# CON_MC_XMC_J12_64PIN.net
KiCad netlist of a schematic drawn in Altium Designer
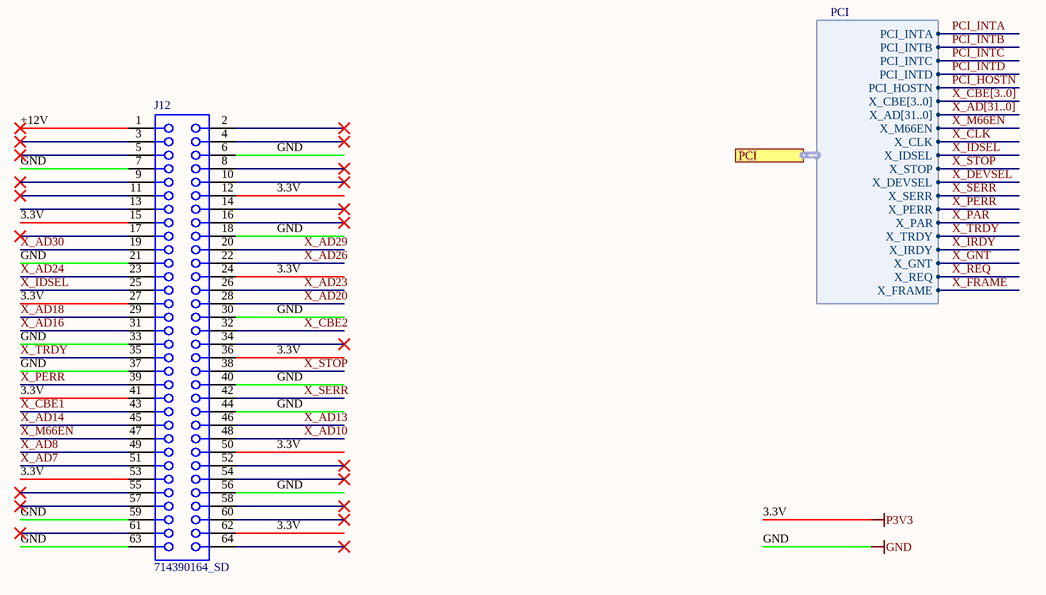
[diagram p0: CON_MC_XMC_J12_64PIN.SchDoc]

(export (version "E")
  (design (tool "Eeschema 10.0.6"))
  (components
    (comp (ref "J12")
      (value "714390164_SD")
      (footprint "BTB1-2V64F")
      (description "Board-to-Board Connector, Vertical, 2-Row, Pitch 1mm, 64-Position, Female")
      (fields (field (name "PUBLISHER") "Altium"))
      (libsource (lib "Altium Shanghai") (part "CMP-0001-00081-1"))
    )
  )
  (nets
    (net (code "21") (name "/+12V") (class "Default")
      (node (ref "J12") (pin "1") (pinfunction "1_1") (pintype "passive+no_connect"))
    )
    (net (code "28") (name "/X_AD7") (class "Default")
      (node (ref "J12") (pin "51") (pinfunction "51_51") (pintype "passive"))
    )
    (net (code "29") (name "/X_AD8") (class "Default")
      (node (ref "J12") (pin "49") (pinfunction "49_49") (pintype "passive"))
    )
    (net (code "30") (name "/X_AD10") (class "Default")
      (node (ref "J12") (pin "48") (pinfunction "48_48") (pintype "passive"))
    )
    (net (code "31") (name "/X_AD13") (class "Default")
      (node (ref "J12") (pin "46") (pinfunction "46_46") (pintype "passive"))
    )
    (net (code "32") (name "/X_AD14") (class "Default")
      (node (ref "J12") (pin "45") (pinfunction "45_45") (pintype "passive"))
    )
    (net (code "33") (name "/X_AD16") (class "Default")
      (node (ref "J12") (pin "31") (pinfunction "31_31") (pintype "passive"))
    )
    (net (code "34") (name "/X_AD18") (class "Default")
      (node (ref "J12") (pin "29") (pinfunction "29_29") (pintype "passive"))
    )
    (net (code "35") (name "/X_AD20") (class "Default")
      (node (ref "J12") (pin "28") (pinfunction "28_28") (pintype "passive"))
    )
    (net (code "36") (name "/X_AD23") (class "Default")
      (node (ref "J12") (pin "26") (pinfunction "26_26") (pintype "passive"))
    )
    (net (code "37") (name "/X_AD24") (class "Default")
      (node (ref "J12") (pin "23") (pinfunction "23_23") (pintype "passive"))
    )
    (net (code "38") (name "/X_AD26") (class "Default")
      (node (ref "J12") (pin "22") (pinfunction "22_22") (pintype "passive"))
    )
    (net (code "39") (name "/X_AD29") (class "Default")
      (node (ref "J12") (pin "20") (pinfunction "20_20") (pintype "passive"))
    )
    (net (code "40") (name "/X_AD30") (class "Default")
      (node (ref "J12") (pin "19") (pinfunction "19_19") (pintype "passive"))
    )
    (net (code "42") (name "/X_CBE1") (class "Default")
      (node (ref "J12") (pin "43") (pinfunction "43_43") (pintype "passive"))
    )
    (net (code "43") (name "/X_CBE2") (class "Default")
      (node (ref "J12") (pin "32") (pinfunction "32_32") (pintype "passive"))
    )
    (net (code "48") (name "/X_IDSEL") (class "Default")
      (node (ref "J12") (pin "25") (pinfunction "25_25") (pintype "passive"))
    )
    (net (code "50") (name "/X_M66EN") (class "Default")
      (node (ref "J12") (pin "47") (pinfunction "47_47") (pintype "passive"))
    )
    (net (code "52") (name "/X_PERR") (class "Default")
      (node (ref "J12") (pin "39") (pinfunction "39_39") (pintype "passive"))
    )
    (net (code "54") (name "/X_SERR") (class "Default")
      (node (ref "J12") (pin "42") (pinfunction "42_42") (pintype "passive"))
    )
    (net (code "55") (name "/X_STOP") (class "Default")
      (node (ref "J12") (pin "38") (pinfunction "38_38") (pintype "passive"))
    )
    (net (code "56") (name "/X_TRDY") (class "Default")
      (node (ref "J12") (pin "35") (pinfunction "35_35") (pintype "passive"))
    )
    (net (code "58") (name "GND") (class "Default")
      (node (ref "J12") (pin "18") (pinfunction "18_18") (pintype "passive"))
      (node (ref "J12") (pin "21") (pinfunction "21_21") (pintype "passive"))
      (node (ref "J12") (pin "30") (pinfunction "30_30") (pintype "passive"))
      (node (ref "J12") (pin "33") (pinfunction "33_33") (pintype "passive"))
      (node (ref "J12") (pin "37") (pinfunction "37_37") (pintype "passive"))
      (node (ref "J12") (pin "40") (pinfunction "40_40") (pintype "passive"))
      (node (ref "J12") (pin "44") (pinfunction "44_44") (pintype "passive"))
      (node (ref "J12") (pin "56") (pinfunction "56_56") (pintype "passive"))
      (node (ref "J12") (pin "59") (pinfunction "59_59") (pintype "passive"))
      (node (ref "J12") (pin "6") (pinfunction "6_6") (pintype "passive"))
      (node (ref "J12") (pin "63") (pinfunction "63_63") (pintype "passive"))
      (node (ref "J12") (pin "7") (pinfunction "7_7") (pintype "passive"))
    )
    (net (code "59") (name "P3V3") (class "Default")
      (node (ref "J12") (pin "12") (pinfunction "12_12") (pintype "passive"))
      (node (ref "J12") (pin "15") (pinfunction "15_15") (pintype "passive"))
      (node (ref "J12") (pin "24") (pinfunction "24_24") (pintype "passive"))
      (node (ref "J12") (pin "27") (pinfunction "27_27") (pintype "passive"))
      (node (ref "J12") (pin "36") (pinfunction "36_36") (pintype "passive"))
      (node (ref "J12") (pin "41") (pinfunction "41_41") (pintype "passive"))
      (node (ref "J12") (pin "50") (pinfunction "50_50") (pintype "passive"))
      (node (ref "J12") (pin "53") (pinfunction "53_53") (pintype "passive"))
      (node (ref "J12") (pin "62") (pinfunction "62_62") (pintype "passive"))
    )
    (net (code "60") (name "unconnected-(J12-Pad2)") (class "Default")
      (node (ref "J12") (pin "2") (pinfunction "2_2") (pintype "passive+no_connect"))
    )
    (net (code "61") (name "unconnected-(J12-Pad3)") (class "Default")
      (node (ref "J12") (pin "3") (pinfunction "3_3") (pintype "passive+no_connect"))
    )
    (net (code "62") (name "unconnected-(J12-Pad4)") (class "Default")
      (node (ref "J12") (pin "4") (pinfunction "4_4") (pintype "passive+no_connect"))
    )
    (net (code "63") (name "unconnected-(J12-Pad5)") (class "Default")
      (node (ref "J12") (pin "5") (pinfunction "5_5") (pintype "passive+no_connect"))
    )
    (net (code "64") (name "unconnected-(J12-Pad8)") (class "Default")
      (node (ref "J12") (pin "8") (pinfunction "8_8") (pintype "passive+no_connect"))
    )
    (net (code "65") (name "unconnected-(J12-Pad9)") (class "Default")
      (node (ref "J12") (pin "9") (pinfunction "9_9") (pintype "passive+no_connect"))
    )
    (net (code "66") (name "unconnected-(J12-Pad10)") (class "Default")
      (node (ref "J12") (pin "10") (pinfunction "10_10") (pintype "passive+no_connect"))
    )
    (net (code "67") (name "unconnected-(J12-Pad11)") (class "Default")
      (node (ref "J12") (pin "11") (pinfunction "11_11") (pintype "passive+no_connect"))
    )
    (net (code "68") (name "unconnected-(J12-Pad13)") (class "Default")
      (node (ref "J12") (pin "13") (pinfunction "13_13") (pintype "passive"))
    )
    (net (code "69") (name "unconnected-(J12-Pad14)") (class "Default")
      (node (ref "J12") (pin "14") (pinfunction "14_14") (pintype "passive+no_connect"))
    )
    (net (code "70") (name "unconnected-(J12-Pad16)") (class "Default")
      (node (ref "J12") (pin "16") (pinfunction "16_16") (pintype "passive+no_connect"))
    )
    (net (code "71") (name "unconnected-(J12-Pad17)") (class "Default")
      (node (ref "J12") (pin "17") (pinfunction "17_17") (pintype "passive+no_connect"))
    )
    (net (code "72") (name "unconnected-(J12-Pad34)") (class "Default")
      (node (ref "J12") (pin "34") (pinfunction "34_34") (pintype "passive+no_connect"))
    )
    (net (code "73") (name "unconnected-(J12-Pad52)") (class "Default")
      (node (ref "J12") (pin "52") (pinfunction "52_52") (pintype "passive+no_connect"))
    )
    (net (code "74") (name "unconnected-(J12-Pad54)") (class "Default")
      (node (ref "J12") (pin "54") (pinfunction "54_54") (pintype "passive+no_connect"))
    )
    (net (code "75") (name "unconnected-(J12-Pad55)") (class "Default")
      (node (ref "J12") (pin "55") (pinfunction "55_55") (pintype "passive+no_connect"))
    )
    (net (code "76") (name "unconnected-(J12-Pad57)") (class "Default")
      (node (ref "J12") (pin "57") (pinfunction "57_57") (pintype "passive+no_connect"))
    )
    (net (code "77") (name "unconnected-(J12-Pad58)") (class "Default")
      (node (ref "J12") (pin "58") (pinfunction "58_58") (pintype "passive+no_connect"))
    )
    (net (code "78") (name "unconnected-(J12-Pad60)") (class "Default")
      (node (ref "J12") (pin "60") (pinfunction "60_60") (pintype "passive+no_connect"))
    )
    (net (code "79") (name "unconnected-(J12-Pad61)") (class "Default")
      (node (ref "J12") (pin "61") (pinfunction "61_61") (pintype "passive+no_connect"))
    )
    (net (code "80") (name "unconnected-(J12-Pad64)") (class "Default")
      (node (ref "J12") (pin "64") (pinfunction "64_64") (pintype "passive+no_connect"))
    )
  )
)
